# x0_current_sense_v0001.net
KiCad netlist of a schematic drawn in EAGLE
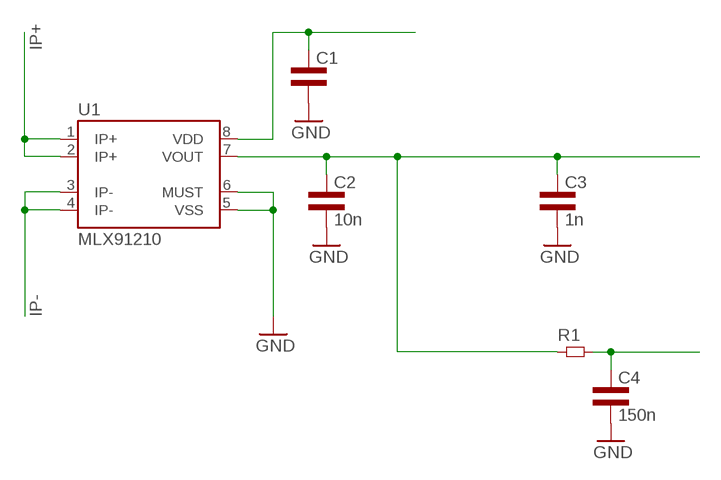
[diagram p0: schematic, sheet 1]

(export (version "E")
  (design (tool "Eeschema 10.0.6"))
  (components
    (comp (ref "C1")
      (value "CAP0603L3")
      (footprint "eagle-import:0603L3")
      (libsource (lib "eagle-import") (part "CAP0603L3"))
    )
    (comp (ref "C2")
      (value "10n")
      (footprint "eagle-import:0603L3")
      (libsource (lib "eagle-import") (part "CAP0603L3"))
    )
    (comp (ref "C3")
      (value "1n")
      (footprint "eagle-import:0603L3")
      (libsource (lib "eagle-import") (part "CAP0603L3"))
    )
    (comp (ref "C4")
      (value "150n")
      (footprint "eagle-import:0603L3")
      (libsource (lib "eagle-import") (part "CAP0603L3"))
    )
    (comp (ref "R1")
      (value "RES0603L3")
      (footprint "eagle-import:0603L3")
      (libsource (lib "eagle-import") (part "RES0603L3"))
    )
    (comp (ref "U1")
      (value "MLX91210")
      (footprint "eagle-import:SOIC-8")
      (libsource (lib "eagle-import") (part "MLX91210"))
    )
  )
  (nets
    (net (code "1") (name "/IP+") (class "Default")
      (node (ref "U1") (pin "1") (pinfunction "IP+_1") (pintype "bidirectional"))
      (node (ref "U1") (pin "2") (pinfunction "IP+_2") (pintype "bidirectional"))
    )
    (net (code "2") (name "/IP-") (class "Default")
      (node (ref "U1") (pin "3") (pinfunction "IP-_3") (pintype "bidirectional"))
      (node (ref "U1") (pin "4") (pinfunction "IP-_4") (pintype "bidirectional"))
    )
    (net (code "3") (name "GND") (class "Default")
      (node (ref "C1") (pin "P$2") (pinfunction "2_P$2") (pintype "bidirectional"))
      (node (ref "C2") (pin "P$2") (pinfunction "2_P$2") (pintype "bidirectional"))
      (node (ref "C3") (pin "P$2") (pinfunction "2_P$2") (pintype "bidirectional"))
      (node (ref "C4") (pin "P$2") (pinfunction "2_P$2") (pintype "bidirectional"))
      (node (ref "U1") (pin "5") (pinfunction "VSS_5") (pintype "bidirectional"))
      (node (ref "U1") (pin "6") (pinfunction "MUST_6") (pintype "bidirectional"))
    )
    (net (code "4") (name "Net-(C1-1)") (class "Default")
      (node (ref "C1") (pin "P$1") (pinfunction "1_P$1") (pintype "bidirectional"))
      (node (ref "U1") (pin "8") (pinfunction "VDD_8") (pintype "bidirectional"))
    )
    (net (code "5") (name "Net-(C2-1)") (class "Default")
      (node (ref "C2") (pin "P$1") (pinfunction "1_P$1") (pintype "bidirectional"))
      (node (ref "C3") (pin "P$1") (pinfunction "1_P$1") (pintype "bidirectional"))
      (node (ref "R1") (pin "P$1") (pinfunction "1_P$1") (pintype "bidirectional"))
      (node (ref "U1") (pin "7") (pinfunction "VOUT_7") (pintype "bidirectional"))
    )
    (net (code "6") (name "Net-(C4-1)") (class "Default")
      (node (ref "C4") (pin "P$1") (pinfunction "1_P$1") (pintype "bidirectional"))
      (node (ref "R1") (pin "P$2") (pinfunction "2_P$2") (pintype "bidirectional"))
    )
  )
)
